# Sheet2.net
KiCad netlist of a schematic drawn in Altium Designer
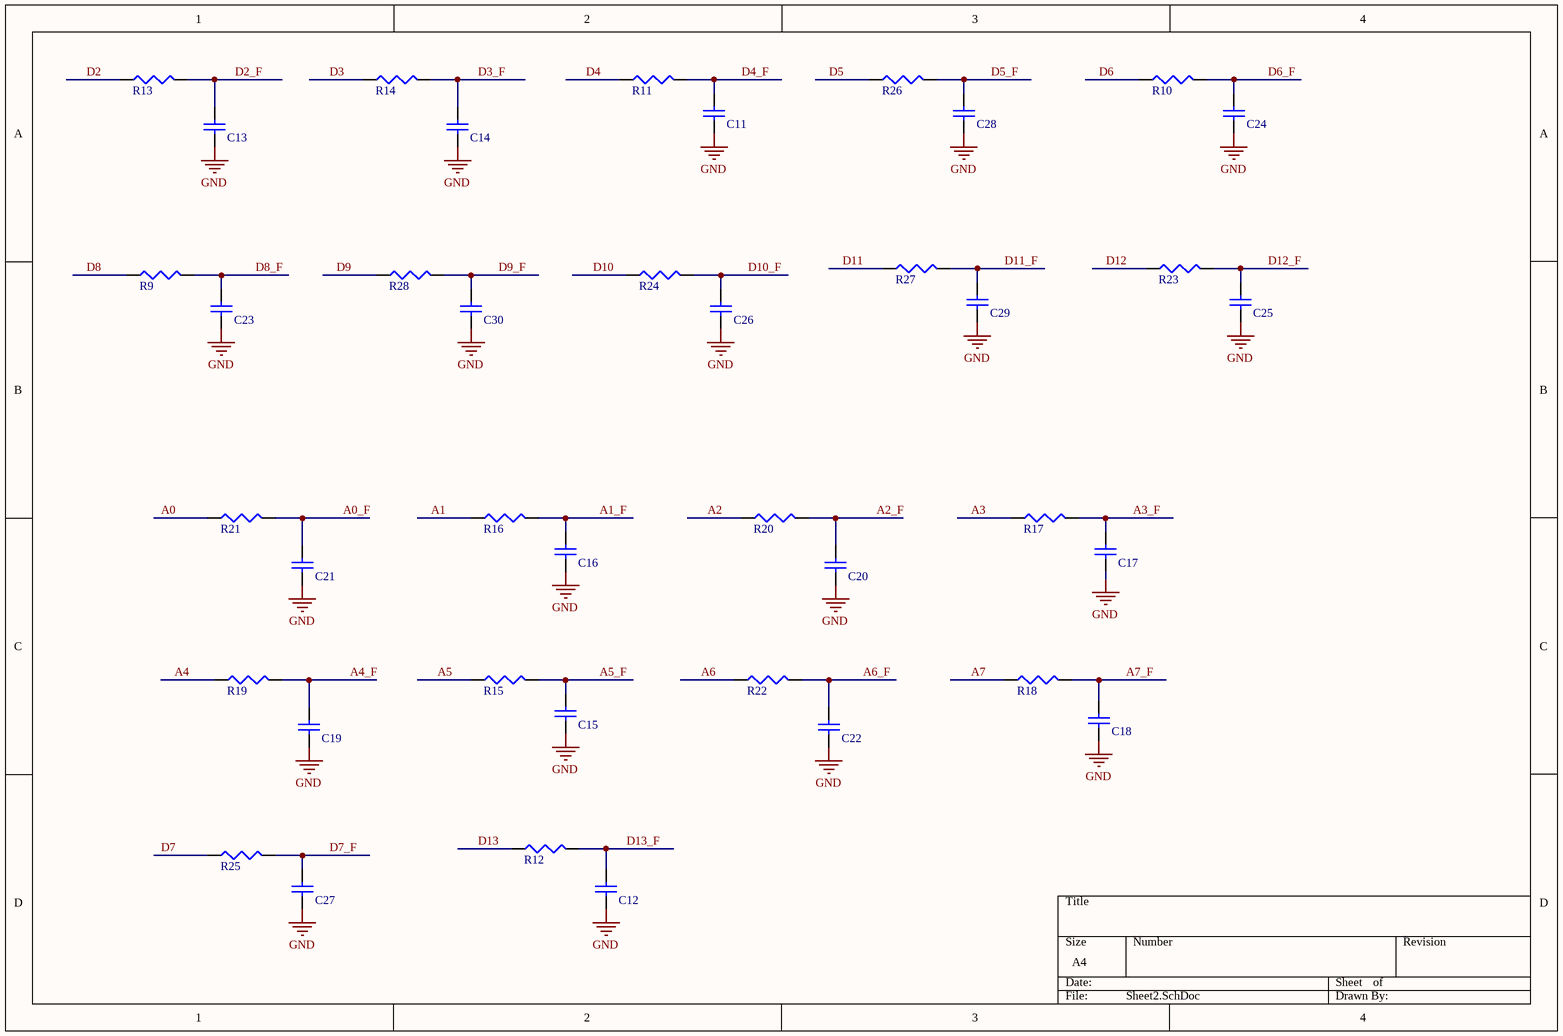
[diagram p0: Sheet2.SchDoc]

(export (version "E")
  (design (tool "Eeschema 10.0.6"))
  (components
    (comp (ref "C11")
      (value "0.1uF")
      (footprint "CAPC1005X60L")
      (description "0.1uF, Ceramic Capacitor")
      (fields (field (name "MANUFACTURER") "VENKEL") (field (name "PARTNUM") "C0402X7R160-104KN"))
      (libsource (lib "Altium_DB") (part "CapStd"))
    )
    (comp (ref "C12")
      (value "0.1uF")
      (footprint "CAPC1005X60L")
      (description "0.1uF, Ceramic Capacitor")
      (fields (field (name "MANUFACTURER") "VENKEL") (field (name "PARTNUM") "C0402X7R160-104KN"))
      (libsource (lib "Altium_DB") (part "CapStd"))
    )
    (comp (ref "C13")
      (value "0.1uF")
      (footprint "CAPC1005X60L")
      (description "0.1uF, Ceramic Capacitor")
      (fields (field (name "MANUFACTURER") "VENKEL") (field (name "PARTNUM") "C0402X7R160-104KN"))
      (libsource (lib "Altium_DB") (part "CapStd"))
    )
    (comp (ref "C14")
      (value "0.1uF")
      (footprint "CAPC1005X60L")
      (description "0.1uF, Ceramic Capacitor")
      (fields (field (name "MANUFACTURER") "VENKEL") (field (name "PARTNUM") "C0402X7R160-104KN"))
      (libsource (lib "Altium_DB") (part "CapStd"))
    )
    (comp (ref "C15")
      (value "0.1uF")
      (footprint "CAPC1005X60L")
      (description "0.1uF, Ceramic Capacitor")
      (fields (field (name "MANUFACTURER") "VENKEL") (field (name "PARTNUM") "C0402X7R160-104KN"))
      (libsource (lib "Altium_DB") (part "CapStd"))
    )
    (comp (ref "C16")
      (value "0.1uF")
      (footprint "CAPC1005X60L")
      (description "0.1uF, Ceramic Capacitor")
      (fields (field (name "MANUFACTURER") "VENKEL") (field (name "PARTNUM") "C0402X7R160-104KN"))
      (libsource (lib "Altium_DB") (part "CapStd"))
    )
    (comp (ref "C17")
      (value "0.1uF")
      (footprint "CAPC1005X60L")
      (description "0.1uF, Ceramic Capacitor")
      (fields (field (name "MANUFACTURER") "VENKEL") (field (name "PARTNUM") "C0402X7R160-104KN"))
      (libsource (lib "Altium_DB") (part "CapStd"))
    )
    (comp (ref "C18")
      (value "0.1uF")
      (footprint "CAPC1005X60L")
      (description "0.1uF, Ceramic Capacitor")
      (fields (field (name "MANUFACTURER") "VENKEL") (field (name "PARTNUM") "C0402X7R160-104KN"))
      (libsource (lib "Altium_DB") (part "CapStd"))
    )
    (comp (ref "C19")
      (value "0.1uF")
      (footprint "CAPC1005X60L")
      (description "0.1uF, Ceramic Capacitor")
      (fields (field (name "MANUFACTURER") "VENKEL") (field (name "PARTNUM") "C0402X7R160-104KN"))
      (libsource (lib "Altium_DB") (part "CapStd"))
    )
    (comp (ref "C20")
      (value "0.1uF")
      (footprint "CAPC1005X60L")
      (description "0.1uF, Ceramic Capacitor")
      (fields (field (name "MANUFACTURER") "VENKEL") (field (name "PARTNUM") "C0402X7R160-104KN"))
      (libsource (lib "Altium_DB") (part "CapStd"))
    )
    (comp (ref "C21")
      (value "0.1uF")
      (footprint "CAPC1005X60L")
      (description "0.1uF, Ceramic Capacitor")
      (fields (field (name "MANUFACTURER") "VENKEL") (field (name "PARTNUM") "C0402X7R160-104KN"))
      (libsource (lib "Altium_DB") (part "CapStd"))
    )
    (comp (ref "C22")
      (value "0.1uF")
      (footprint "CAPC1005X60L")
      (description "0.1uF, Ceramic Capacitor")
      (fields (field (name "MANUFACTURER") "VENKEL") (field (name "PARTNUM") "C0402X7R160-104KN"))
      (libsource (lib "Altium_DB") (part "CapStd"))
    )
    (comp (ref "C23")
      (value "0.1uF")
      (footprint "CAPC1005X60L")
      (description "0.1uF, Ceramic Capacitor")
      (fields (field (name "MANUFACTURER") "VENKEL") (field (name "PARTNUM") "C0402X7R160-104KN"))
      (libsource (lib "Altium_DB") (part "CapStd"))
    )
    (comp (ref "C24")
      (value "0.1uF")
      (footprint "CAPC1005X60L")
      (description "0.1uF, Ceramic Capacitor")
      (fields (field (name "MANUFACTURER") "VENKEL") (field (name "PARTNUM") "C0402X7R160-104KN"))
      (libsource (lib "Altium_DB") (part "CapStd"))
    )
    (comp (ref "C25")
      (value "0.1uF")
      (footprint "CAPC1005X60L")
      (description "0.1uF, Ceramic Capacitor")
      (fields (field (name "MANUFACTURER") "VENKEL") (field (name "PARTNUM") "C0402X7R160-104KN"))
      (libsource (lib "Altium_DB") (part "CapStd"))
    )
    (comp (ref "C26")
      (value "0.1uF")
      (footprint "CAPC1005X60L")
      (description "0.1uF, Ceramic Capacitor")
      (fields (field (name "MANUFACTURER") "VENKEL") (field (name "PARTNUM") "C0402X7R160-104KN"))
      (libsource (lib "Altium_DB") (part "CapStd"))
    )
    (comp (ref "C27")
      (value "0.1uF")
      (footprint "CAPC1005X60L")
      (description "0.1uF, Ceramic Capacitor")
      (fields (field (name "MANUFACTURER") "VENKEL") (field (name "PARTNUM") "C0402X7R160-104KN"))
      (libsource (lib "Altium_DB") (part "CapStd"))
    )
    (comp (ref "C28")
      (value "0.1uF")
      (footprint "CAPC1005X60L")
      (description "0.1uF, Ceramic Capacitor")
      (fields (field (name "MANUFACTURER") "VENKEL") (field (name "PARTNUM") "C0402X7R160-104KN"))
      (libsource (lib "Altium_DB") (part "CapStd"))
    )
    (comp (ref "C29")
      (value "0.1uF")
      (footprint "CAPC1005X60L")
      (description "0.1uF, Ceramic Capacitor")
      (fields (field (name "MANUFACTURER") "VENKEL") (field (name "PARTNUM") "C0402X7R160-104KN"))
      (libsource (lib "Altium_DB") (part "CapStd"))
    )
    (comp (ref "C30")
      (value "0.1uF")
      (footprint "CAPC1005X60L")
      (description "0.1uF, Ceramic Capacitor")
      (fields (field (name "MANUFACTURER") "VENKEL") (field (name "PARTNUM") "C0402X7R160-104KN"))
      (libsource (lib "Altium_DB") (part "CapStd"))
    )
    (comp (ref "R9")
      (value "75R")
      (footprint "RESC1005X40L")
      (description "75R, 1.1mm x 0.5mm, Thick Film Resistor")
      (fields (field (name "MANUFACTURER") "ROYALOHM") (field (name "PARTNUM") "0402WGJ0750T1E"))
      (libsource (lib "Altium_DB") (part "ResStd"))
    )
    (comp (ref "R10")
      (value "75R")
      (footprint "RESC1005X40L")
      (description "75R, 1.1mm x 0.5mm, Thick Film Resistor")
      (fields (field (name "MANUFACTURER") "ROYALOHM") (field (name "PARTNUM") "0402WGJ0750T1E"))
      (libsource (lib "Altium_DB") (part "ResStd"))
    )
    (comp (ref "R11")
      (value "75R")
      (footprint "RESC1005X40L")
      (description "75R, 1.1mm x 0.5mm, Thick Film Resistor")
      (fields (field (name "MANUFACTURER") "ROYALOHM") (field (name "PARTNUM") "0402WGJ0750T1E"))
      (libsource (lib "Altium_DB") (part "ResStd"))
    )
    (comp (ref "R12")
      (value "75R")
      (footprint "RESC1005X40L")
      (description "75R, 1.1mm x 0.5mm, Thick Film Resistor")
      (fields (field (name "MANUFACTURER") "ROYALOHM") (field (name "PARTNUM") "0402WGJ0750T1E"))
      (libsource (lib "Altium_DB") (part "ResStd"))
    )
    (comp (ref "R13")
      (value "75R")
      (footprint "RESC1005X40L")
      (description "75R, 1.1mm x 0.5mm, Thick Film Resistor")
      (fields (field (name "MANUFACTURER") "ROYALOHM") (field (name "PARTNUM") "0402WGJ0750T1E"))
      (libsource (lib "Altium_DB") (part "ResStd"))
    )
    (comp (ref "R14")
      (value "75R")
      (footprint "RESC1005X40L")
      (description "75R, 1.1mm x 0.5mm, Thick Film Resistor")
      (fields (field (name "MANUFACTURER") "ROYALOHM") (field (name "PARTNUM") "0402WGJ0750T1E"))
      (libsource (lib "Altium_DB") (part "ResStd"))
    )
    (comp (ref "R15")
      (value "75R")
      (footprint "RESC1005X40L")
      (description "75R, 1.1mm x 0.5mm, Thick Film Resistor")
      (fields (field (name "MANUFACTURER") "ROYALOHM") (field (name "PARTNUM") "0402WGJ0750T1E"))
      (libsource (lib "Altium_DB") (part "ResStd"))
    )
    (comp (ref "R16")
      (value "75R")
      (footprint "RESC1005X40L")
      (description "75R, 1.1mm x 0.5mm, Thick Film Resistor")
      (fields (field (name "MANUFACTURER") "ROYALOHM") (field (name "PARTNUM") "0402WGJ0750T1E"))
      (libsource (lib "Altium_DB") (part "ResStd"))
    )
    (comp (ref "R17")
      (value "75R")
      (footprint "RESC1005X40L")
      (description "75R, 1.1mm x 0.5mm, Thick Film Resistor")
      (fields (field (name "MANUFACTURER") "ROYALOHM") (field (name "PARTNUM") "0402WGJ0750T1E"))
      (libsource (lib "Altium_DB") (part "ResStd"))
    )
    (comp (ref "R18")
      (value "75R")
      (footprint "RESC1005X40L")
      (description "75R, 1.1mm x 0.5mm, Thick Film Resistor")
      (fields (field (name "MANUFACTURER") "ROYALOHM") (field (name "PARTNUM") "0402WGJ0750T1E"))
      (libsource (lib "Altium_DB") (part "ResStd"))
    )
    (comp (ref "R19")
      (value "75R")
      (footprint "RESC1005X40L")
      (description "75R, 1.1mm x 0.5mm, Thick Film Resistor")
      (fields (field (name "MANUFACTURER") "ROYALOHM") (field (name "PARTNUM") "0402WGJ0750T1E"))
      (libsource (lib "Altium_DB") (part "ResStd"))
    )
    (comp (ref "R20")
      (value "75R")
      (footprint "RESC1005X40L")
      (description "75R, 1.1mm x 0.5mm, Thick Film Resistor")
      (fields (field (name "MANUFACTURER") "ROYALOHM") (field (name "PARTNUM") "0402WGJ0750T1E"))
      (libsource (lib "Altium_DB") (part "ResStd"))
    )
    (comp (ref "R21")
      (value "75R")
      (footprint "RESC1005X40L")
      (description "75R, 1.1mm x 0.5mm, Thick Film Resistor")
      (fields (field (name "MANUFACTURER") "ROYALOHM") (field (name "PARTNUM") "0402WGJ0750T1E"))
      (libsource (lib "Altium_DB") (part "ResStd"))
    )
    (comp (ref "R22")
      (value "75R")
      (footprint "RESC1005X40L")
      (description "75R, 1.1mm x 0.5mm, Thick Film Resistor")
      (fields (field (name "MANUFACTURER") "ROYALOHM") (field (name "PARTNUM") "0402WGJ0750T1E"))
      (libsource (lib "Altium_DB") (part "ResStd"))
    )
    (comp (ref "R23")
      (value "75R")
      (footprint "RESC1005X40L")
      (description "75R, 1.1mm x 0.5mm, Thick Film Resistor")
      (fields (field (name "MANUFACTURER") "ROYALOHM") (field (name "PARTNUM") "0402WGJ0750T1E"))
      (libsource (lib "Altium_DB") (part "ResStd"))
    )
    (comp (ref "R24")
      (value "75R")
      (footprint "RESC1005X40L")
      (description "75R, 1.1mm x 0.5mm, Thick Film Resistor")
      (fields (field (name "MANUFACTURER") "ROYALOHM") (field (name "PARTNUM") "0402WGJ0750T1E"))
      (libsource (lib "Altium_DB") (part "ResStd"))
    )
    (comp (ref "R25")
      (value "75R")
      (footprint "RESC1005X40L")
      (description "75R, 1.1mm x 0.5mm, Thick Film Resistor")
      (fields (field (name "MANUFACTURER") "ROYALOHM") (field (name "PARTNUM") "0402WGJ0750T1E"))
      (libsource (lib "Altium_DB") (part "ResStd"))
    )
    (comp (ref "R26")
      (value "75R")
      (footprint "RESC1005X40L")
      (description "75R, 1.1mm x 0.5mm, Thick Film Resistor")
      (fields (field (name "MANUFACTURER") "ROYALOHM") (field (name "PARTNUM") "0402WGJ0750T1E"))
      (libsource (lib "Altium_DB") (part "ResStd"))
    )
    (comp (ref "R27")
      (value "75R")
      (footprint "RESC1005X40L")
      (description "75R, 1.1mm x 0.5mm, Thick Film Resistor")
      (fields (field (name "MANUFACTURER") "ROYALOHM") (field (name "PARTNUM") "0402WGJ0750T1E"))
      (libsource (lib "Altium_DB") (part "ResStd"))
    )
    (comp (ref "R28")
      (value "75R")
      (footprint "RESC1005X40L")
      (description "75R, 1.1mm x 0.5mm, Thick Film Resistor")
      (fields (field (name "MANUFACTURER") "ROYALOHM") (field (name "PARTNUM") "0402WGJ0750T1E"))
      (libsource (lib "Altium_DB") (part "ResStd"))
    )
  )
  (nets
    (net (code "1") (name "/A0") (class "Default")
      (node (ref "R21") (pin "1") (pinfunction "1_1") (pintype "passive"))
    )
    (net (code "2") (name "/A0_F") (class "Default")
      (node (ref "C21") (pin "2") (pinfunction "2_2") (pintype "passive"))
      (node (ref "R21") (pin "2") (pinfunction "2_2") (pintype "passive"))
    )
    (net (code "3") (name "/A1") (class "Default")
      (node (ref "R16") (pin "1") (pinfunction "1_1") (pintype "passive"))
    )
    (net (code "4") (name "/A1_F") (class "Default")
      (node (ref "C16") (pin "2") (pinfunction "2_2") (pintype "passive"))
      (node (ref "R16") (pin "2") (pinfunction "2_2") (pintype "passive"))
    )
    (net (code "5") (name "/A2") (class "Default")
      (node (ref "R20") (pin "1") (pinfunction "1_1") (pintype "passive"))
    )
    (net (code "6") (name "/A2_F") (class "Default")
      (node (ref "C20") (pin "2") (pinfunction "2_2") (pintype "passive"))
      (node (ref "R20") (pin "2") (pinfunction "2_2") (pintype "passive"))
    )
    (net (code "7") (name "/A3") (class "Default")
      (node (ref "R17") (pin "1") (pinfunction "1_1") (pintype "passive"))
    )
    (net (code "8") (name "/A3_F") (class "Default")
      (node (ref "C17") (pin "2") (pinfunction "2_2") (pintype "passive"))
      (node (ref "R17") (pin "2") (pinfunction "2_2") (pintype "passive"))
    )
    (net (code "9") (name "/A4") (class "Default")
      (node (ref "R19") (pin "1") (pinfunction "1_1") (pintype "passive"))
    )
    (net (code "10") (name "/A4_F") (class "Default")
      (node (ref "C19") (pin "2") (pinfunction "2_2") (pintype "passive"))
      (node (ref "R19") (pin "2") (pinfunction "2_2") (pintype "passive"))
    )
    (net (code "11") (name "/A5") (class "Default")
      (node (ref "R15") (pin "1") (pinfunction "1_1") (pintype "passive"))
    )
    (net (code "12") (name "/A5_F") (class "Default")
      (node (ref "C15") (pin "2") (pinfunction "2_2") (pintype "passive"))
      (node (ref "R15") (pin "2") (pinfunction "2_2") (pintype "passive"))
    )
    (net (code "13") (name "/A6") (class "Default")
      (node (ref "R22") (pin "1") (pinfunction "1_1") (pintype "passive"))
    )
    (net (code "14") (name "/A6_F") (class "Default")
      (node (ref "C22") (pin "2") (pinfunction "2_2") (pintype "passive"))
      (node (ref "R22") (pin "2") (pinfunction "2_2") (pintype "passive"))
    )
    (net (code "15") (name "/A7") (class "Default")
      (node (ref "R18") (pin "1") (pinfunction "1_1") (pintype "passive"))
    )
    (net (code "16") (name "/A7_F") (class "Default")
      (node (ref "C18") (pin "2") (pinfunction "2_2") (pintype "passive"))
      (node (ref "R18") (pin "2") (pinfunction "2_2") (pintype "passive"))
    )
    (net (code "17") (name "/D2") (class "Default")
      (node (ref "R13") (pin "1") (pinfunction "1_1") (pintype "passive"))
    )
    (net (code "18") (name "/D2_F") (class "Default")
      (node (ref "C13") (pin "2") (pinfunction "2_2") (pintype "passive"))
      (node (ref "R13") (pin "2") (pinfunction "2_2") (pintype "passive"))
    )
    (net (code "19") (name "/D3") (class "Default")
      (node (ref "R14") (pin "1") (pinfunction "1_1") (pintype "passive"))
    )
    (net (code "20") (name "/D3_F") (class "Default")
      (node (ref "C14") (pin "2") (pinfunction "2_2") (pintype "passive"))
      (node (ref "R14") (pin "2") (pinfunction "2_2") (pintype "passive"))
    )
    (net (code "21") (name "/D4") (class "Default")
      (node (ref "R11") (pin "1") (pinfunction "1_1") (pintype "passive"))
    )
    (net (code "22") (name "/D4_F") (class "Default")
      (node (ref "C11") (pin "2") (pinfunction "2_2") (pintype "passive"))
      (node (ref "R11") (pin "2") (pinfunction "2_2") (pintype "passive"))
    )
    (net (code "23") (name "/D5") (class "Default")
      (node (ref "R26") (pin "1") (pinfunction "1_1") (pintype "passive"))
    )
    (net (code "24") (name "/D5_F") (class "Default")
      (node (ref "C28") (pin "2") (pinfunction "2_2") (pintype "passive"))
      (node (ref "R26") (pin "2") (pinfunction "2_2") (pintype "passive"))
    )
    (net (code "25") (name "/D6") (class "Default")
      (node (ref "R10") (pin "1") (pinfunction "1_1") (pintype "passive"))
    )
    (net (code "26") (name "/D6_F") (class "Default")
      (node (ref "C24") (pin "2") (pinfunction "2_2") (pintype "passive"))
      (node (ref "R10") (pin "2") (pinfunction "2_2") (pintype "passive"))
    )
    (net (code "27") (name "/D7") (class "Default")
      (node (ref "R25") (pin "1") (pinfunction "1_1") (pintype "passive"))
    )
    (net (code "28") (name "/D7_F") (class "Default")
      (node (ref "C27") (pin "2") (pinfunction "2_2") (pintype "passive"))
      (node (ref "R25") (pin "2") (pinfunction "2_2") (pintype "passive"))
    )
    (net (code "29") (name "/D8") (class "Default")
      (node (ref "R9") (pin "1") (pinfunction "1_1") (pintype "passive"))
    )
    (net (code "30") (name "/D8_F") (class "Default")
      (node (ref "C23") (pin "2") (pinfunction "2_2") (pintype "passive"))
      (node (ref "R9") (pin "2") (pinfunction "2_2") (pintype "passive"))
    )
    (net (code "31") (name "/D9") (class "Default")
      (node (ref "R28") (pin "1") (pinfunction "1_1") (pintype "passive"))
    )
    (net (code "32") (name "/D9_F") (class "Default")
      (node (ref "C30") (pin "2") (pinfunction "2_2") (pintype "passive"))
      (node (ref "R28") (pin "2") (pinfunction "2_2") (pintype "passive"))
    )
    (net (code "33") (name "/D10") (class "Default")
      (node (ref "R24") (pin "1") (pinfunction "1_1") (pintype "passive"))
    )
    (net (code "34") (name "/D10_F") (class "Default")
      (node (ref "C26") (pin "2") (pinfunction "2_2") (pintype "passive"))
      (node (ref "R24") (pin "2") (pinfunction "2_2") (pintype "passive"))
    )
    (net (code "35") (name "/D11") (class "Default")
      (node (ref "R27") (pin "1") (pinfunction "1_1") (pintype "passive"))
    )
    (net (code "36") (name "/D11_F") (class "Default")
      (node (ref "C29") (pin "2") (pinfunction "2_2") (pintype "passive"))
      (node (ref "R27") (pin "2") (pinfunction "2_2") (pintype "passive"))
    )
    (net (code "37") (name "/D12") (class "Default")
      (node (ref "R23") (pin "1") (pinfunction "1_1") (pintype "passive"))
    )
    (net (code "38") (name "/D12_F") (class "Default")
      (node (ref "C25") (pin "2") (pinfunction "2_2") (pintype "passive"))
      (node (ref "R23") (pin "2") (pinfunction "2_2") (pintype "passive"))
    )
    (net (code "39") (name "/D13") (class "Default")
      (node (ref "R12") (pin "1") (pinfunction "1_1") (pintype "passive"))
    )
    (net (code "40") (name "/D13_F") (class "Default")
      (node (ref "C12") (pin "2") (pinfunction "2_2") (pintype "passive"))
      (node (ref "R12") (pin "2") (pinfunction "2_2") (pintype "passive"))
    )
    (net (code "41") (name "GND") (class "Default")
      (node (ref "C11") (pin "1") (pinfunction "1_1") (pintype "passive"))
      (node (ref "C12") (pin "1") (pinfunction "1_1") (pintype "passive"))
      (node (ref "C13") (pin "1") (pinfunction "1_1") (pintype "passive"))
      (node (ref "C14") (pin "1") (pinfunction "1_1") (pintype "passive"))
      (node (ref "C15") (pin "1") (pinfunction "1_1") (pintype "passive"))
      (node (ref "C16") (pin "1") (pinfunction "1_1") (pintype "passive"))
      (node (ref "C17") (pin "1") (pinfunction "1_1") (pintype "passive"))
      (node (ref "C18") (pin "1") (pinfunction "1_1") (pintype "passive"))
      (node (ref "C19") (pin "1") (pinfunction "1_1") (pintype "passive"))
      (node (ref "C20") (pin "1") (pinfunction "1_1") (pintype "passive"))
      (node (ref "C21") (pin "1") (pinfunction "1_1") (pintype "passive"))
      (node (ref "C22") (pin "1") (pinfunction "1_1") (pintype "passive"))
      (node (ref "C23") (pin "1") (pinfunction "1_1") (pintype "passive"))
      (node (ref "C24") (pin "1") (pinfunction "1_1") (pintype "passive"))
      (node (ref "C25") (pin "1") (pinfunction "1_1") (pintype "passive"))
      (node (ref "C26") (pin "1") (pinfunction "1_1") (pintype "passive"))
      (node (ref "C27") (pin "1") (pinfunction "1_1") (pintype "passive"))
      (node (ref "C28") (pin "1") (pinfunction "1_1") (pintype "passive"))
      (node (ref "C29") (pin "1") (pinfunction "1_1") (pintype "passive"))
      (node (ref "C30") (pin "1") (pinfunction "1_1") (pintype "passive"))
    )
  )
)
